# Charger600UM.net
KiCad netlist of a schematic drawn in Altium Designer
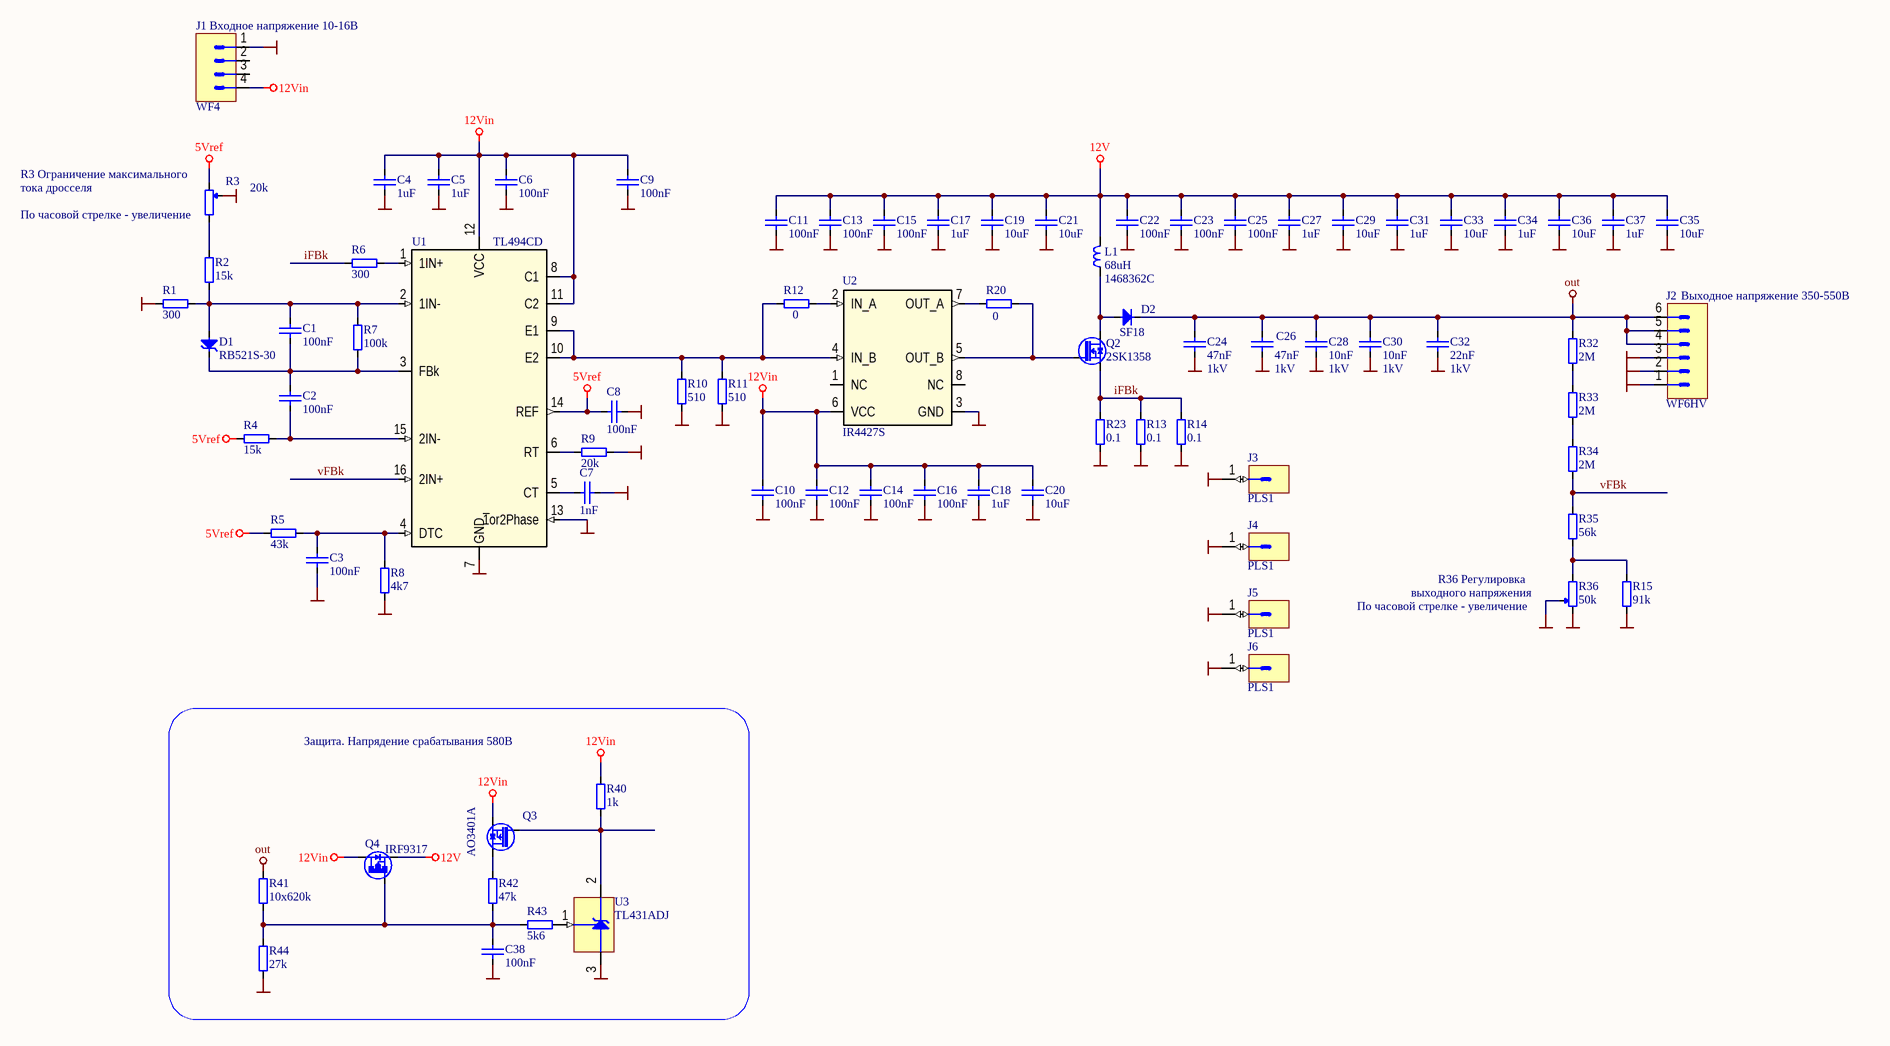
[diagram p0: Charger600UM.SchDoc]

(export (version "E")
  (design (tool "Eeschema 10.0.6"))
  (components
    (comp (ref "C1")
      (value "100nF")
      (footprint "CAPC1608X87N")
      (description "Чип конденсатор 0603")
      (fields (field (name "VOLTAGE") "50V") (field (name "TOLERANCE") "20%"))
      (libsource (lib "DDSintLib") (part "C0603"))
    )
    (comp (ref "C2")
      (value "100nF")
      (footprint "CAPC1608X87N")
      (description "Чип конденсатор 0603")
      (fields (field (name "VOLTAGE") "50V") (field (name "TOLERANCE") "20%"))
      (libsource (lib "DDSintLib") (part "C0603"))
    )
    (comp (ref "C3")
      (value "100nF")
      (footprint "CAPC1608X87N")
      (description "Чип конденсатор 0603")
      (fields (field (name "VOLTAGE") "50V") (field (name "TOLERANCE") "20%"))
      (libsource (lib "DDSintLib") (part "C0603"))
    )
    (comp (ref "C4")
      (value "1uF")
      (footprint "SMD0805CAP")
      (description "Чип конденсатор 0805")
      (fields (field (name "VOLTAGE") "25V") (field (name "TOLERANCE") "20%"))
      (libsource (lib "DDSintLib") (part "C0805"))
    )
    (comp (ref "C5")
      (value "1uF")
      (footprint "SMD0805CAP")
      (description "Чип конденсатор 0805")
      (fields (field (name "VOLTAGE") "25V") (field (name "TOLERANCE") "20%"))
      (libsource (lib "DDSintLib") (part "C0805"))
    )
    (comp (ref "C6")
      (value "100nF")
      (footprint "CAPC1608X87N")
      (description "Чип конденсатор 0603")
      (fields (field (name "VOLTAGE") "50V") (field (name "TOLERANCE") "20%"))
      (libsource (lib "DDSintLib") (part "C0603"))
    )
    (comp (ref "C7")
      (value "1nF")
      (footprint "CAPC1608X87N")
      (description "Чип конденсатор 0603")
      (fields (field (name "VOLTAGE") "50V") (field (name "TOLERANCE") "20%"))
      (libsource (lib "DDSintLib") (part "C0603"))
    )
    (comp (ref "C8")
      (value "100nF")
      (footprint "CAPC1608X87N")
      (description "Чип конденсатор 0603")
      (fields (field (name "VOLTAGE") "50V") (field (name "TOLERANCE") "20%"))
      (libsource (lib "DDSintLib") (part "C0603"))
    )
    (comp (ref "C9")
      (value "100nF")
      (footprint "CAPC1608X87N")
      (description "Чип конденсатор 0603")
      (fields (field (name "VOLTAGE") "50V") (field (name "TOLERANCE") "20%"))
      (libsource (lib "DDSintLib") (part "C0603"))
    )
    (comp (ref "C10")
      (value "100nF")
      (footprint "CAPC1608X87N")
      (description "Чип конденсатор 0603")
      (fields (field (name "VOLTAGE") "50V") (field (name "TOLERANCE") "20%"))
      (libsource (lib "DDSintLib") (part "C0603"))
    )
    (comp (ref "C11")
      (value "100nF")
      (footprint "CAPC1608X87N")
      (description "Чип конденсатор 0603")
      (fields (field (name "VOLTAGE") "50V") (field (name "TOLERANCE") "20%"))
      (libsource (lib "DDSintLib") (part "C0603"))
    )
    (comp (ref "C12")
      (value "100nF")
      (footprint "CAPC1608X87N")
      (description "Чип конденсатор 0603")
      (fields (field (name "VOLTAGE") "50V") (field (name "TOLERANCE") "20%"))
      (libsource (lib "DDSintLib") (part "C0603"))
    )
    (comp (ref "C13")
      (value "100nF")
      (footprint "CAPC1608X87N")
      (description "Чип конденсатор 0603")
      (fields (field (name "VOLTAGE") "50V") (field (name "TOLERANCE") "20%"))
      (libsource (lib "DDSintLib") (part "C0603"))
    )
    (comp (ref "C14")
      (value "100nF")
      (footprint "CAPC1608X87N")
      (description "Чип конденсатор 0603")
      (fields (field (name "VOLTAGE") "50V") (field (name "TOLERANCE") "20%"))
      (libsource (lib "DDSintLib") (part "C0603"))
    )
    (comp (ref "C15")
      (value "100nF")
      (footprint "CAPC1608X87N")
      (description "Чип конденсатор 0603")
      (fields (field (name "VOLTAGE") "50V") (field (name "TOLERANCE") "20%"))
      (libsource (lib "DDSintLib") (part "C0603"))
    )
    (comp (ref "C16")
      (value "100nF")
      (footprint "CAPC1608X87N")
      (description "Чип конденсатор 0603")
      (fields (field (name "VOLTAGE") "50V") (field (name "TOLERANCE") "20%"))
      (libsource (lib "DDSintLib") (part "C0603"))
    )
    (comp (ref "C17")
      (value "1uF")
      (footprint "SMD0805CAP")
      (description "Чип конденсатор 0805")
      (fields (field (name "VOLTAGE") "25V") (field (name "TOLERANCE") "20%"))
      (libsource (lib "DDSintLib") (part "C0805"))
    )
    (comp (ref "C18")
      (value "1uF")
      (footprint "SMD0805CAP")
      (description "Чип конденсатор 0805")
      (fields (field (name "VOLTAGE") "25V") (field (name "TOLERANCE") "20%"))
      (libsource (lib "DDSintLib") (part "C0805"))
    )
    (comp (ref "C19")
      (value "10uF")
      (footprint "CAPC1206")
      (description "Чип конденсатор 1206")
      (fields (field (name "VOLTAGE") "25V") (field (name "TOLERANCE") "1%"))
      (libsource (lib "DDS1") (part "C1206"))
    )
    (comp (ref "C20")
      (value "10uF")
      (footprint "CAPC1206")
      (description "Чип конденсатор 1206")
      (fields (field (name "VOLTAGE") "25V") (field (name "TOLERANCE") "1%"))
      (libsource (lib "DDS1") (part "C1206"))
    )
    (comp (ref "C21")
      (value "10uF")
      (footprint "CAPC1206")
      (description "Чип конденсатор 1206")
      (fields (field (name "VOLTAGE") "25V") (field (name "TOLERANCE") "1%"))
      (libsource (lib "DDS1") (part "C1206"))
    )
    (comp (ref "C22")
      (value "100nF")
      (footprint "CAPC1608X87N")
      (description "Чип конденсатор 0603")
      (fields (field (name "VOLTAGE") "50V") (field (name "TOLERANCE") "20%"))
      (libsource (lib "DDSintLib") (part "C0603"))
    )
    (comp (ref "C23")
      (value "100nF")
      (footprint "CAPC1608X87N")
      (description "Чип конденсатор 0603")
      (fields (field (name "VOLTAGE") "50V") (field (name "TOLERANCE") "20%"))
      (libsource (lib "DDSintLib") (part "C0603"))
    )
    (comp (ref "C24")
      (value "47nF")
      (footprint "CAPR2750-900X3150X1900")
      (description "HV THD capacitor")
      (fields (field (name "TOLERANCE") "+-10%") (field (name "VOLTAGE") "1kV"))
      (libsource (lib "DDSintLib") (part "CBB81"))
    )
    (comp (ref "C25")
      (value "100nF")
      (footprint "CAPC1608X87N")
      (description "Чип конденсатор 0603")
      (fields (field (name "VOLTAGE") "50V") (field (name "TOLERANCE") "20%"))
      (libsource (lib "DDSintLib") (part "C0603"))
    )
    (comp (ref "C26")
      (value "47nF")
      (footprint "CAPR2750-900X3150X1900")
      (description "HV THD capacitor")
      (fields (field (name "TOLERANCE") "+-10%") (field (name "VOLTAGE") "1kV"))
      (libsource (lib "DDSintLib") (part "CBB81"))
    )
    (comp (ref "C27")
      (value "1uF")
      (footprint "SMD0805CAP")
      (description "Чип конденсатор 0805")
      (fields (field (name "VOLTAGE") "25V") (field (name "TOLERANCE") "20%"))
      (libsource (lib "DDSintLib") (part "C0805"))
    )
    (comp (ref "C28")
      (value "10nF")
      (footprint "CAPR1500-900X1800X1750")
      (description "HV THD capacitor")
      (fields (field (name "TOLERANCE") "+-10%") (field (name "VOLTAGE") "1kV"))
      (libsource (lib "DDSintLib") (part "CK45-B3AD"))
    )
    (comp (ref "C29")
      (value "10uF")
      (footprint "CAPC1206")
      (description "Чип конденсатор 1206")
      (fields (field (name "VOLTAGE") "25V") (field (name "TOLERANCE") "1%"))
      (libsource (lib "DDS1") (part "C1206"))
    )
    (comp (ref "C30")
      (value "10nF")
      (footprint "CAPR1500-900X1800X1750")
      (description "HV THD capacitor")
      (fields (field (name "TOLERANCE") "+-10%") (field (name "VOLTAGE") "1kV"))
      (libsource (lib "DDSintLib") (part "CK45-B3AD"))
    )
    (comp (ref "C31")
      (value "1uF")
      (footprint "SMD0805CAP")
      (description "Чип конденсатор 0805")
      (fields (field (name "VOLTAGE") "25V") (field (name "TOLERANCE") "20%"))
      (libsource (lib "DDSintLib") (part "C0805"))
    )
    (comp (ref "C32")
      (value "22nF")
      (footprint "CAPR2250-900X2600X1850")
      (description "HV THD capacitor")
      (fields (field (name "TOLERANCE") "+-10%") (field (name "VOLTAGE") "1kV"))
      (libsource (lib "DDSintLib") (part "CT-81"))
    )
    (comp (ref "C33")
      (value "10uF")
      (footprint "CAPC1206")
      (description "Чип конденсатор 1206")
      (fields (field (name "VOLTAGE") "25V") (field (name "TOLERANCE") "1%"))
      (libsource (lib "DDS1") (part "C1206"))
    )
    (comp (ref "C34")
      (value "1uF")
      (footprint "SMD0805CAP")
      (description "Чип конденсатор 0805")
      (fields (field (name "VOLTAGE") "25V") (field (name "TOLERANCE") "20%"))
      (libsource (lib "DDSintLib") (part "C0805"))
    )
    (comp (ref "C35")
      (value "10uF")
      (footprint "CAPC1206")
      (description "Чип конденсатор 1206")
      (fields (field (name "VOLTAGE") "25V") (field (name "TOLERANCE") "1%"))
      (libsource (lib "DDS1") (part "C1206"))
    )
    (comp (ref "C36")
      (value "10uF")
      (footprint "CAPC1206")
      (description "Чип конденсатор 1206")
      (fields (field (name "VOLTAGE") "25V") (field (name "TOLERANCE") "1%"))
      (libsource (lib "DDS1") (part "C1206"))
    )
    (comp (ref "C37")
      (value "1uF")
      (footprint "SMD0805CAP")
      (description "Чип конденсатор 0805")
      (fields (field (name "VOLTAGE") "25V") (field (name "TOLERANCE") "20%"))
      (libsource (lib "DDSintLib") (part "C0805"))
    )
    (comp (ref "C38")
      (value "100nF")
      (footprint "CAPC1608X87N")
      (description "Чип конденсатор 0603")
      (fields (field (name "VOLTAGE") "50V") (field (name "TOLERANCE") "20%"))
      (libsource (lib "DDSintLib") (part "C0603"))
    )
    (comp (ref "D1")
      (value "RB521S-30")
      (footprint "SODFL1608X65N")
      (description "Чип Шоттки диод")
      (fields (field (name "VOLTAGE") "30V"))
      (libsource (lib "DDSintLib") (part "RB521S-30"))
    )
    (comp (ref "D2")
      (value "SF18")
      (footprint "DIOAD1397W120L700D400")
      (description "HV fast diode")
      (fields (field (name "VOLTAGE") "800"))
      (libsource (lib "DDS1") (part "SF18"))
    )
    (comp (ref "J1")
      (value "WF4")
      (footprint "WF4_2_54")
      (description "Вилка  WF4")
      (libsource (lib "DDSintLib") (part "WF4"))
    )
    (comp (ref "J2")
      (value "WF6HV")
      (footprint "MOLEX_WF6HV")
      (description "Вилка  WF6 HV")
      (libsource (lib "DDSintLib") (part "WF6HV"))
    )
    (comp (ref "J3")
      (value "PLS1")
      (footprint "PLS1")
      (description "Штырь PLS1")
      (libsource (lib "DDSintLib") (part "PLS1"))
    )
    (comp (ref "J4")
      (value "PLS1")
      (footprint "PLS1")
      (description "Штырь PLS1")
      (libsource (lib "DDSintLib") (part "PLS1"))
    )
    (comp (ref "J5")
      (value "PLS1")
      (footprint "PLS1")
      (description "Штырь PLS1")
      (libsource (lib "DDSintLib") (part "PLS1"))
    )
    (comp (ref "J6")
      (value "PLS1")
      (footprint "PLS1")
      (description "Штырь PLS1")
      (libsource (lib "DDSintLib") (part "PLS1"))
    )
    (comp (ref "L1")
      (value "68uH")
      (footprint "muR1468362C")
      (description "THD inductor")
      (fields (field (name "TOLERANCE") "20%") (field (name "DEVICE") "1468362С"))
      (libsource (lib "DDSintLib") (part "1468362С"))
    )
    (comp (ref "Q2")
      (value "2SK1358")
      (footprint "TO-247-v")
      (description "NMOS")
      (fields (field (name "VOLTAGE") "900V"))
      (libsource (lib "DDS1") (part "2SK1358"))
    )
    (comp (ref "Q3")
      (value "AO3401A")
      (footprint "SOT95P229X119-3N")
      (description "PMOS")
      (fields (field (name "VOLTAGE") "-30V"))
      (libsource (lib "DDSintLib") (part "AO3401A"))
    )
    (comp (ref "Q4")
      (value "IRF9317")
      (footprint "SOT95P229X119-3N")
      (description "PMOS")
      (fields (field (name "DEVICE") "IRF9317") (field (name "VOLTAGE") "-30V"))
      (libsource (lib "") (part "AO3401A_1"))
    )
    (comp (ref "R1")
      (value "300")
      (footprint "RESC1608X64N")
      (description "Чип резистор 0603")
      (fields (field (name "TOLERANCE") "1%"))
      (libsource (lib "DDSintLib") (part "R0603"))
    )
    (comp (ref "R2")
      (value "15k")
      (footprint "RESC1608X64N")
      (description "Чип резистор 0603")
      (fields (field (name "TOLERANCE") "1%"))
      (libsource (lib "DDSintLib") (part "R0603"))
    )
    (comp (ref "R3")
      (value "20k")
      (footprint "TRIM_BOURNS_3296Y")
      (description "Trimmer Potentiometer")
      (libsource (lib "DDSintLib") (part "3296"))
    )
    (comp (ref "R4")
      (value "15k")
      (footprint "RESC1608X64N")
      (description "Чип резистор 0603")
      (fields (field (name "TOLERANCE") "1%"))
      (libsource (lib "DDSintLib") (part "R0603"))
    )
    (comp (ref "R5")
      (value "43k")
      (footprint "RESC1608X64N")
      (description "Чип резистор 0603")
      (fields (field (name "TOLERANCE") "1%"))
      (libsource (lib "DDSintLib") (part "R0603"))
    )
    (comp (ref "R6")
      (value "300")
      (footprint "RESC1608X64N")
      (description "Чип резистор 0603")
      (fields (field (name "TOLERANCE") "1%"))
      (libsource (lib "DDSintLib") (part "R0603"))
    )
    (comp (ref "R7")
      (value "100k")
      (footprint "RESC1608X64N")
      (description "Чип резистор 0603")
      (fields (field (name "TOLERANCE") "1%"))
      (libsource (lib "DDSintLib") (part "R0603"))
    )
    (comp (ref "R8")
      (value "4k7")
      (footprint "RESC1608X64N")
      (description "Чип резистор 0603")
      (fields (field (name "TOLERANCE") "1%"))
      (libsource (lib "DDSintLib") (part "R0603"))
    )
    (comp (ref "R9")
      (value "20k")
      (footprint "RESC1608X64N")
      (description "Чип резистор 0603")
      (fields (field (name "TOLERANCE") "1%"))
      (libsource (lib "DDSintLib") (part "R0603"))
    )
    (comp (ref "R10")
      (value "510")
      (footprint "RESC3016X65N")
      (description "Чип резистор 1206")
      (fields (field (name "TOLERANCE") "1%"))
      (libsource (lib "DDSintLib") (part "R1206"))
    )
    (comp (ref "R11")
      (value "510")
      (footprint "RESC3016X65N")
      (description "Чип резистор 1206")
      (fields (field (name "TOLERANCE") "1%"))
      (libsource (lib "DDSintLib") (part "R1206"))
    )
    (comp (ref "R12")
      (value "0")
      (footprint "RESC1608X64N")
      (description "Чип резистор 0603")
      (fields (field (name "TOLERANCE") "1%"))
      (libsource (lib "DDSintLib") (part "R0603"))
    )
    (comp (ref "R13")
      (value "0.1")
      (footprint "SMD0805RES")
      (description "Чип резистор 0805")
      (fields (field (name "TOLERANCE") "1%"))
      (libsource (lib "DDSintLib") (part "R0805"))
    )
    (comp (ref "R14")
      (value "0.1")
      (footprint "SMD0805RES")
      (description "Чип резистор 0805")
      (fields (field (name "TOLERANCE") "1%"))
      (libsource (lib "DDSintLib") (part "R0805"))
    )
    (comp (ref "R15")
      (value "91k")
      (footprint "RESC1608X64N")
      (description "Чип резистор 0603")
      (fields (field (name "TOLERANCE") "1%"))
      (libsource (lib "DDSintLib") (part "R0603"))
    )
    (comp (ref "R20")
      (value "0")
      (footprint "RESC1608X64N")
      (description "Чип резистор 0603")
      (fields (field (name "TOLERANCE") "1%"))
      (libsource (lib "DDSintLib") (part "R0603"))
    )
    (comp (ref "R23")
      (value "0.1")
      (footprint "SMD0805RES")
      (description "Чип резистор 0805")
      (fields (field (name "TOLERANCE") "1%"))
      (libsource (lib "DDSintLib") (part "R0805"))
    )
    (comp (ref "R32")
      (value "2M")
      (footprint "RES1016-360X210")
      (description "250mW THD resistor")
      (fields (field (name "TOLERANCE") "1%"))
      (libsource (lib "DDSintLib") (part "CF-1/4W"))
    )
    (comp (ref "R33")
      (value "2M")
      (footprint "RES1016-360X210")
      (description "250mW THD resistor")
      (fields (field (name "TOLERANCE") "1%"))
      (libsource (lib "DDSintLib") (part "CF-1/4W"))
    )
    (comp (ref "R34")
      (value "2M")
      (footprint "RES1016-360X210")
      (description "250mW THD resistor")
      (fields (field (name "TOLERANCE") "1%"))
      (libsource (lib "DDSintLib") (part "CF-1/4W"))
    )
    (comp (ref "R35")
      (value "56k")
      (footprint "RESC1608X64N")
      (description "Чип резистор 0603")
      (fields (field (name "TOLERANCE") "1%"))
      (libsource (lib "DDSintLib") (part "R0603"))
    )
    (comp (ref "R36")
      (value "50k")
      (footprint "TRIM_BOURNS_3296Y")
      (description "Trimmer Potentiometer")
      (libsource (lib "DDSintLib") (part "3296"))
    )
    (comp (ref "R40")
      (value "1k")
      (footprint "RESC1608X64N")
      (description "Чип резистор 0603")
      (fields (field (name "TOLERANCE") "1%"))
      (libsource (lib "DDSintLib") (part "R0603"))
    )
    (comp (ref "R41")
      (value "10x620k")
      (footprint "RES1016-360X210")
      (description "250mW THD resistor")
      (fields (field (name "TOLERANCE") "1%"))
      (libsource (lib "DDSintLib") (part "CF-1/4W"))
    )
    (comp (ref "R42")
      (value "47k")
      (footprint "RESC1608X64N")
      (description "Чип резистор 0603")
      (fields (field (name "TOLERANCE") "1%"))
      (libsource (lib "DDSintLib") (part "R0603"))
    )
    (comp (ref "R43")
      (value "5k6")
      (footprint "RESC1608X64N")
      (description "Чип резистор 0603")
      (fields (field (name "TOLERANCE") "1%"))
      (libsource (lib "DDSintLib") (part "R0603"))
    )
    (comp (ref "R44")
      (value "27k")
      (footprint "RESC1608X64N")
      (description "Чип резистор 0603")
      (fields (field (name "TOLERANCE") "1%"))
      (libsource (lib "DDSintLib") (part "R0603"))
    )
    (comp (ref "U1")
      (value "TL494CD")
      (footprint "SOIC127P780X200-16N")
      (description "PWM Controller")
      (libsource (lib "DDS1") (part "TL494"))
    )
    (comp (ref "U2")
      (value "IR4427S")
      (footprint "SOIC127P600X175-8N")
      (description "Double low side non inverting MOSFET driver")
      (libsource (lib "DDS1") (part "IR4427"))
    )
    (comp (ref "U3")
      (value "TL431ADJ")
      (footprint "SOT95P229X119-3N")
      (description "Shunt reference")
      (libsource (lib "DDSintLib") (part "TL431"))
    )
  )
  (nets
    (net (code "1") (name "/iFBk") (class "Default")
      (node (ref "Q2") (pin "3") (pinfunction "S_3") (pintype "passive"))
      (node (ref "R13") (pin "2") (pinfunction "2_2") (pintype "passive"))
      (node (ref "R14") (pin "2") (pinfunction "2_2") (pintype "passive"))
      (node (ref "R23") (pin "2") (pinfunction "2_2") (pintype "passive"))
      (node (ref "R6") (pin "2") (pinfunction "2_2") (pintype "passive"))
    )
    (net (code "2") (name "/vFBk") (class "Default")
      (node (ref "R34") (pin "1") (pinfunction "1_1") (pintype "passive"))
      (node (ref "R35") (pin "2") (pinfunction "2_2") (pintype "passive"))
      (node (ref "U1") (pin "16") (pinfunction "2IN+_16") (pintype "input"))
    )
    (net (code "3") (name "5Vref") (class "Default")
      (node (ref "C8") (pin "2") (pinfunction "2_2") (pintype "passive"))
      (node (ref "R3") (pin "1") (pinfunction "1_1") (pintype "passive"))
      (node (ref "R4") (pin "2") (pinfunction "2_2") (pintype "passive"))
      (node (ref "R5") (pin "2") (pinfunction "2_2") (pintype "passive"))
      (node (ref "U1") (pin "14") (pinfunction "REF_14") (pintype "output"))
    )
    (net (code "4") (name "12V") (class "Default")
      (node (ref "C11") (pin "2") (pinfunction "2_2") (pintype "passive"))
      (node (ref "C13") (pin "2") (pinfunction "2_2") (pintype "passive"))
      (node (ref "C15") (pin "2") (pinfunction "2_2") (pintype "passive"))
      (node (ref "C17") (pin "2") (pinfunction "2_2") (pintype "passive"))
      (node (ref "C19") (pin "2") (pinfunction "2_2") (pintype "passive"))
      (node (ref "C21") (pin "2") (pinfunction "2_2") (pintype "passive"))
      (node (ref "C22") (pin "2") (pinfunction "2_2") (pintype "passive"))
      (node (ref "C23") (pin "2") (pinfunction "2_2") (pintype "passive"))
      (node (ref "C25") (pin "2") (pinfunction "2_2") (pintype "passive"))
      (node (ref "C27") (pin "2") (pinfunction "2_2") (pintype "passive"))
      (node (ref "C29") (pin "2") (pinfunction "2_2") (pintype "passive"))
      (node (ref "C31") (pin "2") (pinfunction "2_2") (pintype "passive"))
      (node (ref "C33") (pin "2") (pinfunction "2_2") (pintype "passive"))
      (node (ref "C34") (pin "2") (pinfunction "2_2") (pintype "passive"))
      (node (ref "C35") (pin "2") (pinfunction "2_2") (pintype "passive"))
      (node (ref "C36") (pin "2") (pinfunction "2_2") (pintype "passive"))
      (node (ref "C37") (pin "2") (pinfunction "2_2") (pintype "passive"))
      (node (ref "L1") (pin "2") (pinfunction "2_2") (pintype "passive"))
      (node (ref "Q4") (pin "2") (pinfunction "S_2") (pintype "passive"))
    )
    (net (code "5") (name "12Vin") (class "Default")
      (node (ref "C10") (pin "2") (pinfunction "2_2") (pintype "passive"))
      (node (ref "C12") (pin "2") (pinfunction "2_2") (pintype "passive"))
      (node (ref "C14") (pin "2") (pinfunction "2_2") (pintype "passive"))
      (node (ref "C16") (pin "2") (pinfunction "2_2") (pintype "passive"))
      (node (ref "C18") (pin "2") (pinfunction "2_2") (pintype "passive"))
      (node (ref "C20") (pin "2") (pinfunction "2_2") (pintype "passive"))
      (node (ref "C4") (pin "2") (pinfunction "2_2") (pintype "passive"))
      (node (ref "C5") (pin "2") (pinfunction "2_2") (pintype "passive"))
      (node (ref "C6") (pin "2") (pinfunction "2_2") (pintype "passive"))
      (node (ref "C9") (pin "2") (pinfunction "2_2") (pintype "passive"))
      (node (ref "J1") (pin "4") (pinfunction "4_4") (pintype "bidirectional"))
      (node (ref "Q3") (pin "2") (pinfunction "S_2") (pintype "passive"))
      (node (ref "Q4") (pin "3") (pinfunction "D_3") (pintype "passive"))
      (node (ref "R40") (pin "2") (pinfunction "2_2") (pintype "passive"))
      (node (ref "U1") (pin "11") (pinfunction "C2_11") (pintype "open_collector"))
      (node (ref "U1") (pin "12") (pinfunction "VCC_12") (pintype "power_in"))
      (node (ref "U1") (pin "8") (pinfunction "C1_8") (pintype "open_collector"))
      (node (ref "U2") (pin "6") (pinfunction "VCC_6") (pintype "power_in"))
    )
    (net (code "6") (name "GND") (class "Default")
      (node (ref "C10") (pin "1") (pinfunction "1_1") (pintype "passive"))
      (node (ref "C11") (pin "1") (pinfunction "1_1") (pintype "passive"))
      (node (ref "C12") (pin "1") (pinfunction "1_1") (pintype "passive"))
      (node (ref "C13") (pin "1") (pinfunction "1_1") (pintype "passive"))
      (node (ref "C14") (pin "1") (pinfunction "1_1") (pintype "passive"))
      (node (ref "C15") (pin "1") (pinfunction "1_1") (pintype "passive"))
      (node (ref "C16") (pin "1") (pinfunction "1_1") (pintype "passive"))
      (node (ref "C17") (pin "1") (pinfunction "1_1") (pintype "passive"))
      (node (ref "C18") (pin "1") (pinfunction "1_1") (pintype "passive"))
      (node (ref "C19") (pin "1") (pinfunction "1_1") (pintype "passive"))
      (node (ref "C20") (pin "1") (pinfunction "1_1") (pintype "passive"))
      (node (ref "C21") (pin "1") (pinfunction "1_1") (pintype "passive"))
      (node (ref "C22") (pin "1") (pinfunction "1_1") (pintype "passive"))
      (node (ref "C23") (pin "1") (pinfunction "1_1") (pintype "passive"))
      (node (ref "C24") (pin "1") (pinfunction "1_1") (pintype "passive"))
      (node (ref "C25") (pin "1") (pinfunction "1_1") (pintype "passive"))
      (node (ref "C26") (pin "1") (pinfunction "1_1") (pintype "passive"))
      (node (ref "C27") (pin "1") (pinfunction "1_1") (pintype "passive"))
      (node (ref "C28") (pin "1") (pinfunction "1_1") (pintype "passive"))
      (node (ref "C29") (pin "1") (pinfunction "1_1") (pintype "passive"))
      (node (ref "C3") (pin "1") (pinfunction "1_1") (pintype "passive"))
      (node (ref "C30") (pin "1") (pinfunction "1_1") (pintype "passive"))
      (node (ref "C31") (pin "1") (pinfunction "1_1") (pintype "passive"))
      (node (ref "C32") (pin "1") (pinfunction "1_1") (pintype "passive"))
      (node (ref "C33") (pin "1") (pinfunction "1_1") (pintype "passive"))
      (node (ref "C34") (pin "1") (pinfunction "1_1") (pintype "passive"))
      (node (ref "C35") (pin "1") (pinfunction "1_1") (pintype "passive"))
      (node (ref "C36") (pin "1") (pinfunction "1_1") (pintype "passive"))
      (node (ref "C37") (pin "1") (pinfunction "1_1") (pintype "passive"))
      (node (ref "C38") (pin "1") (pinfunction "1_1") (pintype "passive"))
      (node (ref "C4") (pin "1") (pinfunction "1_1") (pintype "passive"))
      (node (ref "C5") (pin "1") (pinfunction "1_1") (pintype "passive"))
      (node (ref "C6") (pin "1") (pinfunction "1_1") (pintype "passive"))
      (node (ref "C7") (pin "1") (pinfunction "1_1") (pintype "passive"))
      (node (ref "C8") (pin "1") (pinfunction "1_1") (pintype "passive"))
      (node (ref "C9") (pin "1") (pinfunction "1_1") (pintype "passive"))
      (node (ref "J1") (pin "1") (pinfunction "1_1") (pintype "bidirectional"))
      (node (ref "J2") (pin "1") (pinfunction "1_1") (pintype "bidirectional"))
      (node (ref "J2") (pin "2") (pinfunction "2_2") (pintype "bidirectional"))
      (node (ref "J2") (pin "3") (pinfunction "3_3") (pintype "bidirectional"))
      (node (ref "J3") (pin "1") (pinfunction "1_1") (pintype "bidirectional"))
      (node (ref "J4") (pin "1") (pinfunction "1_1") (pintype "bidirectional"))
      (node (ref "J5") (pin "1") (pinfunction "1_1") (pintype "bidirectional"))
      (node (ref "J6") (pin "1") (pinfunction "1_1") (pintype "bidirectional"))
      (node (ref "R1") (pin "2") (pinfunction "2_2") (pintype "passive"))
      (node (ref "R10") (pin "1") (pinfunction "1_1") (pintype "passive"))
      (node (ref "R11") (pin "1") (pinfunction "1_1") (pintype "passive"))
      (node (ref "R13") (pin "1") (pinfunction "1_1") (pintype "passive"))
      (node (ref "R14") (pin "1") (pinfunction "1_1") (pintype "passive"))
      (node (ref "R15") (pin "1") (pinfunction "1_1") (pintype "passive"))
      (node (ref "R23") (pin "1") (pinfunction "1_1") (pintype "passive"))
      (node (ref "R3") (pin "2") (pinfunction "W_2") (pintype "passive"))
      (node (ref "R36") (pin "1") (pinfunction "1_1") (pintype "passive"))
      (node (ref "R36") (pin "2") (pinfunction "W_2") (pintype "passive"))
      (node (ref "R44") (pin "1") (pinfunction "1_1") (pintype "passive"))
      (node (ref "R8") (pin "1") (pinfunction "1_1") (pintype "passive"))
      (node (ref "R9") (pin "1") (pinfunction "1_1") (pintype "passive"))
      (node (ref "U1") (pin "13") (pinfunction "~{1}or2Phase_13") (pintype "input"))
      (node (ref "U1") (pin "7") (pinfunction "GND_7") (pintype "power_in"))
      (node (ref "U2") (pin "3") (pinfunction "GND_3") (pintype "power_in"))
      (node (ref "U3") (pin "3") (pinfunction "Anode_3") (pintype "passive"))
    )
    (net (code "7") (name "Net-(D1-A)") (class "Default")
      (node (ref "C1") (pin "2") (pinfunction "2_2") (pintype "passive"))
      (node (ref "D1") (pin "2") (pinfunction "A_2") (pintype "passive"))
      (node (ref "R1") (pin "1") (pinfunction "1_1") (pintype "passive"))
      (node (ref "R2") (pin "1") (pinfunction "1_1") (pintype "passive"))
      (node (ref "R7") (pin "2") (pinfunction "2_2") (pintype "passive"))
      (node (ref "U1") (pin "2") (pinfunction "1IN-_2") (pintype "input"))
    )
    (net (code "8") (name "Net-(D1-C)") (class "Default")
      (node (ref "C1") (pin "1") (pinfunction "1_1") (pintype "passive"))
      (node (ref "C2") (pin "2") (pinfunction "2_2") (pintype "passive"))
      (node (ref "D1") (pin "1") (pinfunction "C_1") (pintype "passive"))
      (node (ref "R7") (pin "1") (pinfunction "1_1") (pintype "passive"))
      (node (ref "U1") (pin "3") (pinfunction "FBk_3") (pintype "passive"))
    )
    (net (code "9") (name "Net-(D2-A)") (class "Default")
      (node (ref "D2") (pin "2") (pinfunction "A_2") (pintype "passive"))
      (node (ref "L1") (pin "1") (pinfunction "1_1") (pintype "passive"))
      (node (ref "Q2") (pin "2") (pinfunction "D_2") (pintype "passive"))
    )
    (net (code "10") (name "Net-(Q2-G)") (class "Default")
      (node (ref "Q2") (pin "1") (pinfunction "G_1") (pintype "passive"))
      (node (ref "R20") (pin "2") (pinfunction "2_2") (pintype "passive"))
      (node (ref "U2") (pin "5") (pinfunction "OUT_B_5") (pintype "output"))
    )
    (net (code "11") (name "Net-(Q3-D)") (class "Default")
      (node (ref "Q3") (pin "3") (pinfunction "D_3") (pintype "passive"))
      (node (ref "R42") (pin "2") (pinfunction "2_2") (pintype "passive"))
    )
    (net (code "12") (name "Net-(Q3-G)") (class "Default")
      (node (ref "Q3") (pin "1") (pinfunction "G_1") (pintype "passive"))
      (node (ref "R40") (pin "1") (pinfunction "1_1") (pintype "passive"))
      (node (ref "U3") (pin "2") (pinfunction "Cathode_2") (pintype "passive"))
    )
    (net (code "13") (name "Net-(Q4-G)") (class "Default")
      (node (ref "C38") (pin "2") (pinfunction "2_2") (pintype "passive"))
      (node (ref "Q4") (pin "1") (pinfunction "G_1") (pintype "passive"))
      (node (ref "R41") (pin "1") (pinfunction "1_1") (pintype "passive"))
      (node (ref "R42") (pin "1") (pinfunction "1_1") (pintype "passive"))
      (node (ref "R43") (pin "2") (pinfunction "2_2") (pintype "passive"))
      (node (ref "R44") (pin "2") (pinfunction "2_2") (pintype "passive"))
    )
    (net (code "14") (name "Net-(R2-Pad2)") (class "Default")
      (node (ref "R2") (pin "2") (pinfunction "2_2") (pintype "passive"))
      (node (ref "R3") (pin "3") (pinfunction "3_3") (pintype "passive"))
    )
    (net (code "15") (name "Net-(R15-Pad2)") (class "Default")
      (node (ref "R15") (pin "2") (pinfunction "2_2") (pintype "passive"))
      (node (ref "R35") (pin "1") (pinfunction "1_1") (pintype "passive"))
      (node (ref "R36") (pin "3") (pinfunction "3_3") (pintype "passive"))
    )
    (net (code "16") (name "Net-(R32-Pad1)") (class "Default")
      (node (ref "R32") (pin "1") (pinfunction "1_1") (pintype "passive"))
      (node (ref "R33") (pin "2") (pinfunction "2_2") (pintype "passive"))
    )
    (net (code "17") (name "Net-(R33-Pad1)") (class "Default")
      (node (ref "R33") (pin "1") (pinfunction "1_1") (pintype "passive"))
      (node (ref "R34") (pin "2") (pinfunction "2_2") (pintype "passive"))
    )
    (net (code "18") (name "Net-(U1-1IN+)") (class "Default")
      (node (ref "R6") (pin "1") (pinfunction "1_1") (pintype "passive"))
      (node (ref "U1") (pin "1") (pinfunction "1IN+_1") (pintype "input"))
    )
    (net (code "19") (name "Net-(U1-2IN-)") (class "Default")
      (node (ref "C2") (pin "1") (pinfunction "1_1") (pintype "passive"))
      (node (ref "R4") (pin "1") (pinfunction "1_1") (pintype "passive"))
      (node (ref "U1") (pin "15") (pinfunction "2IN-_15") (pintype "input"))
    )
    (net (code "20") (name "Net-(U1-CT)") (class "Default")
      (node (ref "C7") (pin "2") (pinfunction "2_2") (pintype "passive"))
      (node (ref "U1") (pin "5") (pinfunction "CT_5") (pintype "passive"))
    )
    (net (code "21") (name "Net-(U1-DTC)") (class "Default")
      (node (ref "C3") (pin "2") (pinfunction "2_2") (pintype "passive"))
      (node (ref "R5") (pin "1") (pinfunction "1_1") (pintype "passive"))
      (node (ref "R8") (pin "2") (pinfunction "2_2") (pintype "passive"))
      (node (ref "U1") (pin "4") (pinfunction "DTC_4") (pintype "input"))
    )
    (net (code "22") (name "Net-(U1-E1)") (class "Default")
      (node (ref "R10") (pin "2") (pinfunction "2_2") (pintype "passive"))
      (node (ref "R11") (pin "2") (pinfunction "2_2") (pintype "passive"))
      (node (ref "R12") (pin "1") (pinfunction "1_1") (pintype "passive"))
      (node (ref "U1") (pin "10") (pinfunction "E2_10") (pintype "open_emitter"))
      (node (ref "U1") (pin "9") (pinfunction "E1_9") (pintype "open_emitter"))
      (node (ref "U2") (pin "4") (pinfunction "IN_B_4") (pintype "input"))
    )
    (net (code "23") (name "Net-(U1-RT)") (class "Default")
      (node (ref "R9") (pin "2") (pinfunction "2_2") (pintype "passive"))
      (node (ref "U1") (pin "6") (pinfunction "RT_6") (pintype "passive"))
    )
    (net (code "24") (name "Net-(U2-IN_A)") (class "Default")
      (node (ref "R12") (pin "2") (pinfunction "2_2") (pintype "passive"))
      (node (ref "U2") (pin "2") (pinfunction "IN_A_2") (pintype "input"))
    )
    (net (code "25") (name "Net-(U2-OUT_A)") (class "Default")
      (node (ref "R20") (pin "1") (pinfunction "1_1") (pintype "passive"))
      (node (ref "U2") (pin "7") (pinfunction "OUT_A_7") (pintype "output"))
    )
    (net (code "26") (name "Net-(U3-REF)") (class "Default")
      (node (ref "R43") (pin "1") (pinfunction "1_1") (pintype "passive"))
      (node (ref "U3") (pin "1") (pinfunction "REF_1") (pintype "input"))
    )
    (net (code "27") (name "out") (class "Default")
      (node (ref "C24") (pin "2") (pinfunction "2_2") (pintype "passive"))
      (node (ref "C26") (pin "2") (pinfunction "2_2") (pintype "passive"))
      (node (ref "C28") (pin "2") (pinfunction "2_2") (pintype "passive"))
      (node (ref "C30") (pin "2") (pinfunction "2_2") (pintype "passive"))
      (node (ref "C32") (pin "2") (pinfunction "2_2") (pintype "passive"))
      (node (ref "D2") (pin "1") (pinfunction "C_1") (pintype "passive"))
      (node (ref "J2") (pin "4") (pinfunction "4_4") (pintype "bidirectional"))
      (node (ref "J2") (pin "5") (pinfunction "5_5") (pintype "bidirectional"))
      (node (ref "J2") (pin "6") (pinfunction "6_6") (pintype "bidirectional"))
      (node (ref "R32") (pin "2") (pinfunction "2_2") (pintype "passive"))
      (node (ref "R41") (pin "2") (pinfunction "2_2") (pintype "passive"))
    )
    (net (code "28") (name "unconnected-(J1-Pad2)") (class "Default")
      (node (ref "J1") (pin "2") (pinfunction "2_2") (pintype "bidirectional"))
    )
    (net (code "29") (name "unconnected-(J1-Pad3)") (class "Default")
      (node (ref "J1") (pin "3") (pinfunction "3_3") (pintype "bidirectional"))
    )
    (net (code "30") (name "unconnected-(U2-NC-Pad1)") (class "Default")
      (node (ref "U2") (pin "1") (pinfunction "NC_1") (pintype "passive"))
    )
    (net (code "31") (name "unconnected-(U2-NC-Pad8)") (class "Default")
      (node (ref "U2") (pin "8") (pinfunction "NC_8") (pintype "passive"))
    )
  )
)
